# EEZ_tester_r1B3.net
KiCad netlist of a schematic drawn in EAGLE
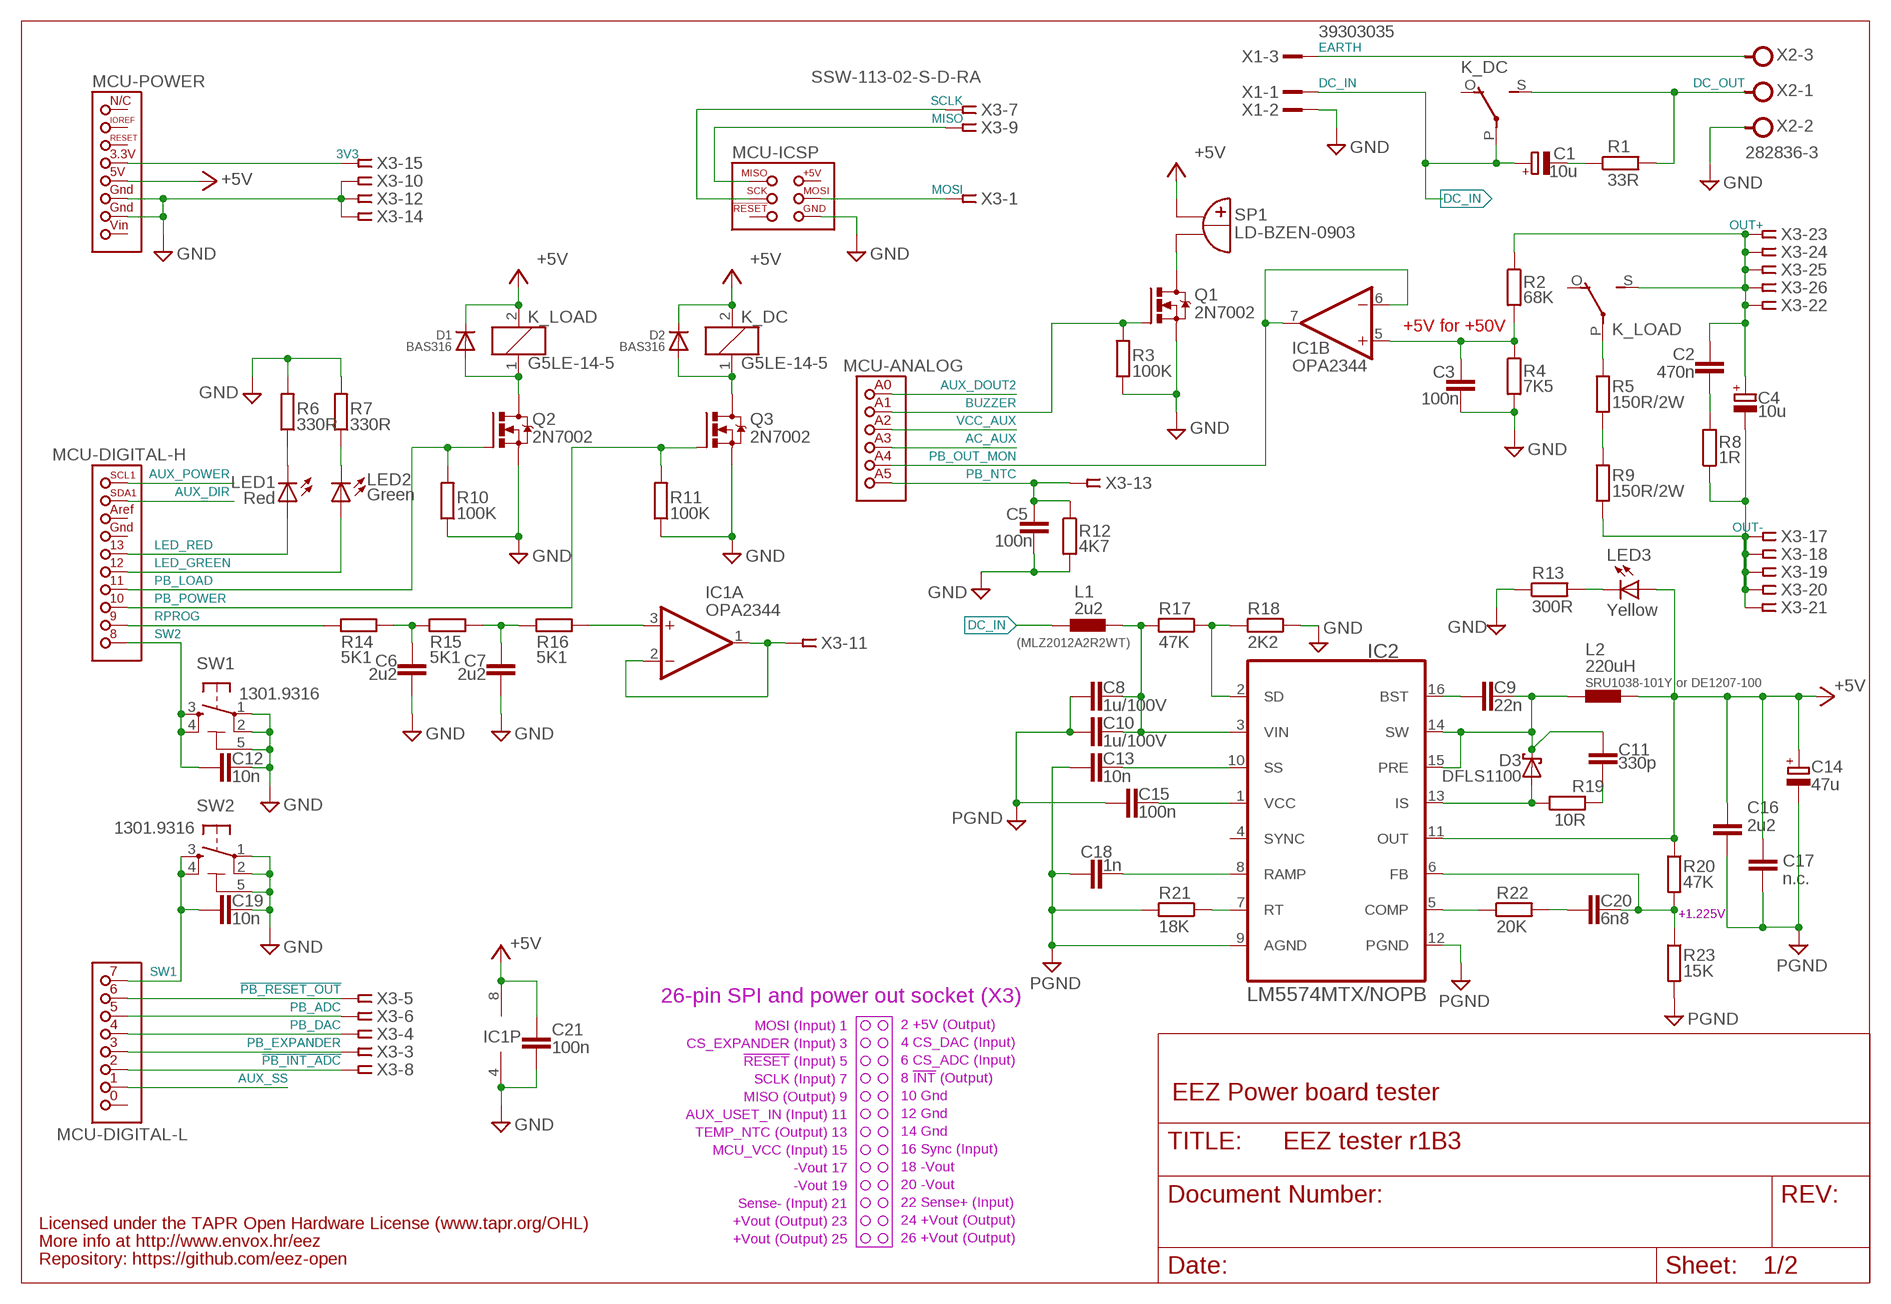
[diagram p0: schematic, sheet 1]
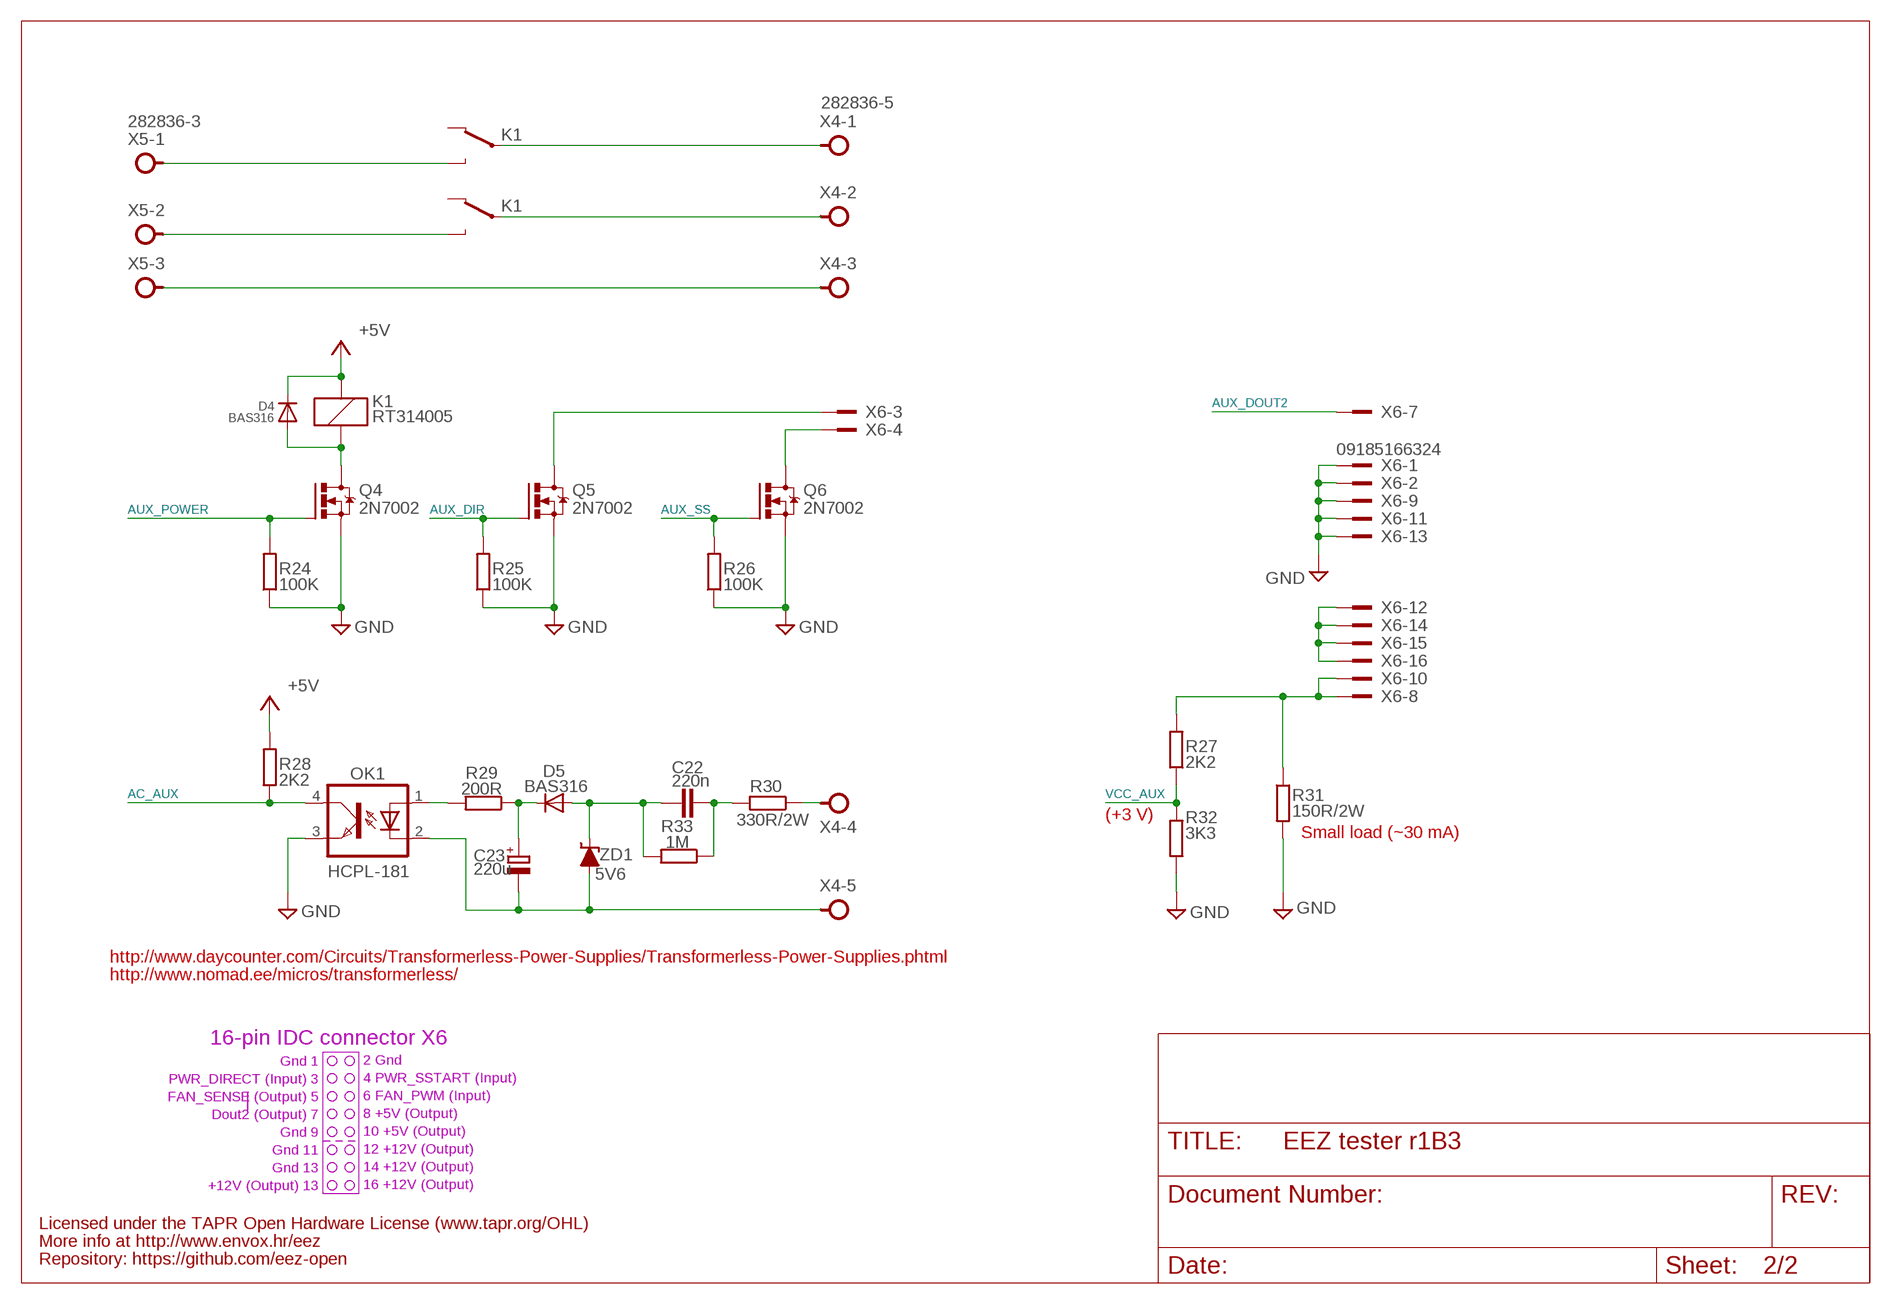
[diagram p1: schematic, sheet 2]

(export (version "E")
  (design (tool "Eeschema 10.0.6"))
  (components
    (comp (ref "C22")
      (value "220n")
      (footprint "eagle-import:C150-084X183")
      (libsource (lib "eagle-import") (part "C-EU150-084X183"))
    )
    (comp (ref "C23")
      (value "220u")
      (footprint "eagle-import:CAPAE660X610N")
      (libsource (lib "eagle-import") (part "ECAPPANASONIC_H"))
    )
    (comp (ref "D4")
      (value "BAS316")
      (footprint "eagle-import:SOD323-W")
      (libsource (lib "eagle-import") (part "DIODE-SOD323-W"))
    )
    (comp (ref "D5")
      (value "BAS316")
      (footprint "eagle-import:SOD323-W")
      (libsource (lib "eagle-import") (part "DIODE-SOD323-W"))
    )
    (comp (ref "K1")
      (value "RT314005")
      (footprint "eagle-import:RT-C_016A5_ROUND")
      (libsource (lib "eagle-import") (part "RELAY_RT314012-2"))
    )
    (comp (ref "OK1")
      (value "HCPL-181")
      (footprint "eagle-import:HCPL-181")
      (libsource (lib "eagle-import") (part "HCPL-181"))
    )
    (comp (ref "Q4")
      (value "2N7002")
      (footprint "eagle-import:SOT103P240X110-3N")
      (fields
        (field (name "MPN") "2N7002-7-F")
        (field (name "MPN_1") "2N7002-7-F")
        (field (name "OC_FARNELL") "1713823")
        (field (name "OC_NEWARK") "25R5679")
        (field (name "PACKAGE") "SOT-23-3")
        (field (name "SUPPLIER") "DIODES INC.")
      )
      (libsource (lib "eagle-import") (part "2N7002"))
    )
    (comp (ref "Q5")
      (value "2N7002")
      (footprint "eagle-import:SOT103P240X110-3N")
      (fields
        (field (name "MPN") "2N7002-7-F")
        (field (name "MPN_1") "2N7002-7-F")
        (field (name "OC_FARNELL") "1713823")
        (field (name "OC_NEWARK") "25R5679")
        (field (name "PACKAGE") "SOT-23-3")
        (field (name "SUPPLIER") "DIODES INC.")
      )
      (libsource (lib "eagle-import") (part "2N7002"))
    )
    (comp (ref "Q6")
      (value "2N7002")
      (footprint "eagle-import:SOT103P240X110-3N")
      (fields
        (field (name "MPN") "2N7002-7-F")
        (field (name "MPN_1") "2N7002-7-F")
        (field (name "OC_FARNELL") "1713823")
        (field (name "OC_NEWARK") "25R5679")
        (field (name "PACKAGE") "SOT-23-3")
        (field (name "SUPPLIER") "DIODES INC.")
      )
      (libsource (lib "eagle-import") (part "2N7002"))
    )
    (comp (ref "R24")
      (value "100K")
      (footprint "eagle-import:R0805")
      (libsource (lib "eagle-import") (part "R-EU_R0805"))
    )
    (comp (ref "R25")
      (value "100K")
      (footprint "eagle-import:R0805")
      (libsource (lib "eagle-import") (part "R-EU_R0805"))
    )
    (comp (ref "R26")
      (value "100K")
      (footprint "eagle-import:R0805")
      (libsource (lib "eagle-import") (part "R-EU_R0805"))
    )
    (comp (ref "R27")
      (value "2K2")
      (footprint "eagle-import:R0805")
      (libsource (lib "eagle-import") (part "R-EU_R0805"))
    )
    (comp (ref "R28")
      (value "2K2")
      (footprint "eagle-import:R0805")
      (libsource (lib "eagle-import") (part "R-EU_R0805"))
    )
    (comp (ref "R29")
      (value "200R")
      (footprint "eagle-import:R0805")
      (libsource (lib "eagle-import") (part "R-EU_R0805"))
    )
    (comp (ref "R30")
      (value "330R/2W")
      (footprint "eagle-import:R2512")
      (libsource (lib "eagle-import") (part "R-EU_R2512"))
    )
    (comp (ref "R31")
      (value "150R/2W")
      (footprint "eagle-import:R2512")
      (libsource (lib "eagle-import") (part "R-EU_R2512"))
    )
    (comp (ref "R32")
      (value "3K3")
      (footprint "eagle-import:R0805")
      (libsource (lib "eagle-import") (part "R-EU_R0805"))
    )
    (comp (ref "R33")
      (value "1M")
      (footprint "eagle-import:R0805")
      (libsource (lib "eagle-import") (part "R-EU_R0805"))
    )
    (comp (ref "X4")
      (value "282836-5")
      (footprint "eagle-import:TBLOCK5.0_5")
      (libsource (lib "eagle-import") (part "TBLOCK5.0_5A"))
    )
    (comp (ref "X5")
      (value "282836-3")
      (footprint "eagle-import:TBLOCK5.0_3")
      (libsource (lib "eagle-import") (part "TBLOCK5.0_3A"))
    )
    (comp (ref "X6")
      (value "09185166324")
      (footprint "eagle-import:IDC-16PIN")
      (libsource (lib "eagle-import") (part "IDC-16PIN"))
    )
    (comp (ref "ZD1")
      (value "5V6")
      (footprint "eagle-import:SOD323-W")
      (libsource (lib "eagle-import") (part "ZENER-DIODESOD323"))
    )
    (comp (ref "C1")
      (value "10u")
      (footprint "eagle-import:PANASONIC_C")
      (libsource (lib "eagle-import") (part "MyLib6_ECAPPANASONIC_C"))
    )
    (comp (ref "C2")
      (value "470n")
      (footprint "eagle-import:C0805")
      (libsource (lib "eagle-import") (part "C-EUC0805"))
    )
    (comp (ref "C3")
      (value "100n")
      (footprint "eagle-import:C0603")
      (libsource (lib "eagle-import") (part "C-EUC0603"))
    )
    (comp (ref "C4")
      (value "10u")
      (footprint "eagle-import:PANASONIC_C")
      (libsource (lib "eagle-import") (part "MyLib6_ECAPPANASONIC_C"))
    )
    (comp (ref "C5")
      (value "100n")
      (footprint "eagle-import:C0603")
      (libsource (lib "eagle-import") (part "C-EUC0603"))
    )
    (comp (ref "C6")
      (value "2u2")
      (footprint "eagle-import:C0805")
      (libsource (lib "eagle-import") (part "C-EUC0805"))
    )
    (comp (ref "C7")
      (value "2u2")
      (footprint "eagle-import:C0805")
      (libsource (lib "eagle-import") (part "C-EUC0805"))
    )
    (comp (ref "C8")
      (value "1u/100V")
      (footprint "eagle-import:C1206")
      (libsource (lib "eagle-import") (part "C-EUC1206"))
    )
    (comp (ref "C9")
      (value "22n")
      (footprint "eagle-import:C0805")
      (libsource (lib "eagle-import") (part "C-EUC0805"))
    )
    (comp (ref "C10")
      (value "1u/100V")
      (footprint "eagle-import:C1206")
      (libsource (lib "eagle-import") (part "C-EUC1206"))
    )
    (comp (ref "C11")
      (value "330p")
      (footprint "eagle-import:C0805")
      (libsource (lib "eagle-import") (part "C-EUC0805"))
    )
    (comp (ref "C12")
      (value "10n")
      (footprint "eagle-import:C0805")
      (libsource (lib "eagle-import") (part "C-EUC0805"))
    )
    (comp (ref "C13")
      (value "10n")
      (footprint "eagle-import:C0805")
      (libsource (lib "eagle-import") (part "C-EUC0805"))
    )
    (comp (ref "C14")
      (value "47u")
      (footprint "eagle-import:CAPAE660X610N")
      (libsource (lib "eagle-import") (part "ECAPPANASONIC_H"))
    )
    (comp (ref "C15")
      (value "100n")
      (footprint "eagle-import:C0603")
      (libsource (lib "eagle-import") (part "C-EUC0603"))
    )
    (comp (ref "C16")
      (value "2u2")
      (footprint "eagle-import:C0805")
      (libsource (lib "eagle-import") (part "C-EUC0805"))
    )
    (comp (ref "C17")
      (value "n.c.")
      (footprint "eagle-import:C0805")
      (libsource (lib "eagle-import") (part "C-EUC0805"))
    )
    (comp (ref "C18")
      (value "1n")
      (footprint "eagle-import:C0805")
      (libsource (lib "eagle-import") (part "C-EUC0805"))
    )
    (comp (ref "C19")
      (value "10n")
      (footprint "eagle-import:C0805")
      (libsource (lib "eagle-import") (part "C-EUC0805"))
    )
    (comp (ref "C20")
      (value "6n8")
      (footprint "eagle-import:C0805")
      (libsource (lib "eagle-import") (part "C-EUC0805"))
    )
    (comp (ref "C21")
      (value "100n")
      (footprint "eagle-import:C0603")
      (libsource (lib "eagle-import") (part "C-EUC0603"))
    )
    (comp (ref "D1")
      (value "BAS316")
      (footprint "eagle-import:SOD323-W")
      (libsource (lib "eagle-import") (part "DIODE-SOD323-W"))
    )
    (comp (ref "D2")
      (value "BAS316")
      (footprint "eagle-import:SOD323-W")
      (libsource (lib "eagle-import") (part "DIODE-SOD323-W"))
    )
    (comp (ref "D3")
      (value "DFLS1100")
      (footprint "eagle-import:SOD123")
      (libsource (lib "eagle-import") (part "SCHOTTKYSOD123"))
    )
    (comp (ref "IC1")
      (value "OPA2344")
      (footprint "eagle-import:SOIC127P600X173-8N")
      (libsource (lib "eagle-import") (part "TL072SOIC8"))
    )
    (comp (ref "IC2")
      (value "LM5574MTX/NOPB")
      (footprint "eagle-import:SOP65P640X110-16N")
      (fields (field (name "MPN") "LM5574MT"))
      (libsource (lib "eagle-import") (part "LM5574"))
    )
    (comp (ref "K_DC")
      (value "G5LE-14-5")
      (footprint "eagle-import:G5LE")
      (fields (field (name "OC_FARNELL") "unknown") (field (name "OC_NEWARK") "unknown"))
      (libsource (lib "eagle-import") (part "G5LE"))
    )
    (comp (ref "K_LOAD")
      (value "G5LE-14-5")
      (footprint "eagle-import:G5LE")
      (libsource (lib "eagle-import") (part "G5LE"))
    )
    (comp (ref "L1")
      (value "2u2")
      (footprint "eagle-import:0805")
      (libsource (lib "eagle-import") (part "L-EU0805"))
    )
    (comp (ref "L2")
      (value "220uH")
      (footprint "eagle-import:MSS1278")
      (libsource (lib "eagle-import") (part "COILCRAFT_MSS1278"))
    )
    (comp (ref "LED1")
      (value "Red")
      (footprint "eagle-import:LED3MM")
      (libsource (lib "eagle-import") (part "LED3MM"))
    )
    (comp (ref "LED2")
      (value "Green")
      (footprint "eagle-import:LED3MM")
      (libsource (lib "eagle-import") (part "LED3MM"))
    )
    (comp (ref "LED3")
      (value "Yellow")
      (footprint "eagle-import:LED3MM")
      (libsource (lib "eagle-import") (part "LED3MM"))
    )
    (comp (ref "MCU")
      (value "ARDUINO_LEONARDO")
      (footprint "eagle-import:ARDUINO_LEONARDO")
      (libsource (lib "eagle-import") (part "ARDUINO_LEONARDO"))
    )
    (comp (ref "Q1")
      (value "2N7002")
      (footprint "eagle-import:SOT103P240X110-3N")
      (fields (field (name "MPN") "2N7002-7-F"))
      (libsource (lib "eagle-import") (part "2N7002"))
    )
    (comp (ref "Q2")
      (value "2N7002")
      (footprint "eagle-import:SOT103P240X110-3N")
      (fields
        (field (name "MPN") "2N7002-7-F")
        (field (name "MPN_1") "2N7002-7-F")
        (field (name "OC_FARNELL") "1713823")
        (field (name "OC_NEWARK") "25R5679")
        (field (name "PACKAGE") "SOT-23-3")
        (field (name "SUPPLIER") "DIODES INC.")
      )
      (libsource (lib "eagle-import") (part "2N7002"))
    )
    (comp (ref "Q3")
      (value "2N7002")
      (footprint "eagle-import:SOT103P240X110-3N")
      (fields
        (field (name "MPN") "2N7002-7-F")
        (field (name "MPN_1") "2N7002-7-F")
        (field (name "OC_FARNELL") "1713823")
        (field (name "OC_NEWARK") "25R5679")
        (field (name "PACKAGE") "SOT-23-3")
        (field (name "SUPPLIER") "DIODES INC.")
      )
      (libsource (lib "eagle-import") (part "2N7002"))
    )
    (comp (ref "R1")
      (value "33R")
      (footprint "eagle-import:R0805")
      (libsource (lib "eagle-import") (part "R-EU_R0805"))
    )
    (comp (ref "R2")
      (value "68K")
      (footprint "eagle-import:R0805")
      (libsource (lib "eagle-import") (part "R-EU_R0805"))
    )
    (comp (ref "R3")
      (value "100K")
      (footprint "eagle-import:R0805")
      (libsource (lib "eagle-import") (part "R-EU_R0805"))
    )
    (comp (ref "R4")
      (value "7K5")
      (footprint "eagle-import:R0805")
      (libsource (lib "eagle-import") (part "R-EU_R0805"))
    )
    (comp (ref "R5")
      (value "150R/2W")
      (footprint "eagle-import:0617_22")
      (libsource (lib "eagle-import") (part "R-EU_0617/22"))
    )
    (comp (ref "R6")
      (value "330R")
      (footprint "eagle-import:R0805")
      (libsource (lib "eagle-import") (part "R-EU_R0805"))
    )
    (comp (ref "R7")
      (value "330R")
      (footprint "eagle-import:R0805")
      (libsource (lib "eagle-import") (part "R-EU_R0805"))
    )
    (comp (ref "R8")
      (value "1R")
      (footprint "eagle-import:R0805")
      (libsource (lib "eagle-import") (part "R-EU_R0805"))
    )
    (comp (ref "R9")
      (value "150R/2W")
      (footprint "eagle-import:0617_22")
      (libsource (lib "eagle-import") (part "R-EU_0617/22"))
    )
    (comp (ref "R10")
      (value "100K")
      (footprint "eagle-import:R0805")
      (libsource (lib "eagle-import") (part "R-EU_R0805"))
    )
    (comp (ref "R11")
      (value "100K")
      (footprint "eagle-import:R0805")
      (libsource (lib "eagle-import") (part "R-EU_R0805"))
    )
    (comp (ref "R12")
      (value "4K7")
      (footprint "eagle-import:R0805")
      (libsource (lib "eagle-import") (part "R-EU_R0805"))
    )
    (comp (ref "R13")
      (value "300R")
      (footprint "eagle-import:R0805")
      (libsource (lib "eagle-import") (part "R-EU_R0805"))
    )
    (comp (ref "R14")
      (value "5K1")
      (footprint "eagle-import:R0805")
      (libsource (lib "eagle-import") (part "R-EU_R0805"))
    )
    (comp (ref "R15")
      (value "5K1")
      (footprint "eagle-import:R0805")
      (libsource (lib "eagle-import") (part "R-EU_R0805"))
    )
    (comp (ref "R16")
      (value "5K1")
      (footprint "eagle-import:R0805")
      (libsource (lib "eagle-import") (part "R-EU_R0805"))
    )
    (comp (ref "R17")
      (value "47K")
      (footprint "eagle-import:R0805")
      (libsource (lib "eagle-import") (part "R-EU_R0805"))
    )
    (comp (ref "R18")
      (value "2K2")
      (footprint "eagle-import:R0805")
      (libsource (lib "eagle-import") (part "R-EU_R0805"))
    )
    (comp (ref "R19")
      (value "10R")
      (footprint "eagle-import:R1206")
      (libsource (lib "eagle-import") (part "R-EU_R1206"))
    )
    (comp (ref "R20")
      (value "47K")
      (footprint "eagle-import:R0805")
      (libsource (lib "eagle-import") (part "R-EU_R0805"))
    )
    (comp (ref "R21")
      (value "18K")
      (footprint "eagle-import:R0805")
      (libsource (lib "eagle-import") (part "R-EU_R0805"))
    )
    (comp (ref "R22")
      (value "20K")
      (footprint "eagle-import:R0805")
      (libsource (lib "eagle-import") (part "R-EU_R0805"))
    )
    (comp (ref "R23")
      (value "15K")
      (footprint "eagle-import:R0805")
      (libsource (lib "eagle-import") (part "R-EU_R0805"))
    )
    (comp (ref "SP1")
      (value "LD-BZEN-0903")
      (footprint "eagle-import:LD-BZEN-0903")
      (libsource (lib "eagle-import") (part "BUZZER-2"))
    )
    (comp (ref "SW1")
      (value "1301.9316")
      (footprint "eagle-import:TACTM-6XN")
      (libsource (lib "eagle-import") (part "TACT_SW"))
    )
    (comp (ref "SW2")
      (value "1301.9316")
      (footprint "eagle-import:TACTM-6XN")
      (libsource (lib "eagle-import") (part "TACT_SW"))
    )
    (comp (ref "X1")
      (value "39303035")
      (footprint "eagle-import:MINIFIT_6659-3")
      (libsource (lib "eagle-import") (part "MINIFIT-3PIN"))
    )
    (comp (ref "X2")
      (value "282836-3")
      (footprint "eagle-import:TBLOCK5.0_3")
      (libsource (lib "eagle-import") (part "TBLOCK5.0_3A"))
    )
    (comp (ref "X3")
      (value "SSW-113-02-S-D-RA")
      (footprint "eagle-import:TSW-113-02-S-D-RA")
      (libsource (lib "eagle-import") (part "SSW-113-02-S-D-RA"))
    )
  )
  (nets
    (net (code "1") (name "+5V") (class "Default")
      (node (ref "C14") (pin "1") (pinfunction "+_1") (pintype "passive"))
      (node (ref "C16") (pin "1") (pinfunction "1_1") (pintype "passive"))
      (node (ref "C17") (pin "1") (pinfunction "1_1") (pintype "passive"))
      (node (ref "C21") (pin "1") (pinfunction "1_1") (pintype "passive"))
      (node (ref "D1") (pin "C") (pinfunction "C_C") (pintype "passive"))
      (node (ref "D2") (pin "C") (pinfunction "C_C") (pintype "passive"))
      (node (ref "D4") (pin "C") (pinfunction "C_C") (pintype "passive"))
      (node (ref "IC1") (pin "8") (pinfunction "V+_8") (pintype "power_in"))
      (node (ref "IC2") (pin "11") (pinfunction "OUT_11") (pintype "output"))
      (node (ref "K1") (pin "A2") (pinfunction "C1_A2") (pintype "passive"))
      (node (ref "K_DC") (pin "2") (pinfunction "2_2") (pintype "passive"))
      (node (ref "K_LOAD") (pin "2") (pinfunction "2_2") (pintype "passive"))
      (node (ref "L2") (pin "2") (pinfunction "2_2") (pintype "passive"))
      (node (ref "LED3") (pin "A") (pinfunction "A_A") (pintype "passive"))
      (node (ref "MCU") (pin "5V") (pinfunction "5V_5V") (pintype "bidirectional"))
      (node (ref "R20") (pin "1") (pinfunction "1_1") (pintype "passive"))
      (node (ref "R28") (pin "2") (pinfunction "2_2") (pintype "passive"))
      (node (ref "SP1") (pin "+B") (pinfunction "+_+B") (pintype "passive"))
    )
    (net (code "2") (name "3V3") (class "Default")
      (node (ref "MCU") (pin "3.3V") (pinfunction "3V3_3.3V") (pintype "bidirectional"))
      (node (ref "X3") (pin "15") (pinfunction "1_15") (pintype "passive"))
    )
    (net (code "3") (name "AC_AUX") (class "Default")
      (node (ref "MCU") (pin "A3") (pinfunction "ADC3_A3") (pintype "bidirectional"))
      (node (ref "OK1") (pin "4") (pinfunction "COL_4") (pintype "passive"))
      (node (ref "R28") (pin "1") (pinfunction "1_1") (pintype "passive"))
    )
    (net (code "4") (name "AUX_DIR") (class "Default")
      (node (ref "MCU") (pin "SDA1") (pinfunction "SDA1_SDA1") (pintype "bidirectional"))
      (node (ref "Q5") (pin "1") (pinfunction "G_1") (pintype "passive"))
      (node (ref "R25") (pin "2") (pinfunction "2_2") (pintype "passive"))
    )
    (net (code "5") (name "AUX_DOUT2") (class "Default")
      (node (ref "MCU") (pin "A0") (pinfunction "ADC0_A0") (pintype "bidirectional"))
      (node (ref "X6") (pin "7") (pinfunction "1_7") (pintype "passive"))
    )
    (net (code "6") (name "AUX_POWER") (class "Default")
      (node (ref "MCU") (pin "SCL1") (pinfunction "SCL1_SCL1") (pintype "bidirectional"))
      (node (ref "Q4") (pin "1") (pinfunction "G_1") (pintype "passive"))
      (node (ref "R24") (pin "2") (pinfunction "2_2") (pintype "passive"))
    )
    (net (code "7") (name "AUX_SS") (class "Default")
      (node (ref "MCU") (pin "1") (pinfunction "1(PE1)_1") (pintype "bidirectional"))
      (node (ref "Q6") (pin "1") (pinfunction "G_1") (pintype "passive"))
      (node (ref "R26") (pin "2") (pinfunction "2_2") (pintype "passive"))
    )
    (net (code "8") (name "BUZZER") (class "Default")
      (node (ref "MCU") (pin "A1") (pinfunction "ADC1_A1") (pintype "bidirectional"))
      (node (ref "Q1") (pin "1") (pinfunction "G_1") (pintype "passive"))
      (node (ref "R3") (pin "2") (pinfunction "2_2") (pintype "passive"))
    )
    (net (code "9") (name "DC_IN") (class "Default")
      (node (ref "C1") (pin "1") (pinfunction "+_1") (pintype "passive"))
      (node (ref "K_DC") (pin "P") (pinfunction "P_P") (pintype "passive"))
      (node (ref "L1") (pin "1") (pinfunction "1_1") (pintype "passive"))
      (node (ref "X1") (pin "1") (pinfunction "1_1") (pintype "passive"))
    )
    (net (code "10") (name "DC_OUT") (class "Default")
      (node (ref "K_DC") (pin "S") (pinfunction "S_S") (pintype "passive"))
      (node (ref "R1") (pin "2") (pinfunction "2_2") (pintype "passive"))
      (node (ref "X2") (pin "1") (pinfunction "1_1") (pintype "bidirectional"))
    )
    (net (code "11") (name "EARTH") (class "Default")
      (node (ref "X1") (pin "3") (pinfunction "1_3") (pintype "passive"))
      (node (ref "X2") (pin "3") (pinfunction "1_3") (pintype "bidirectional"))
    )
    (net (code "12") (name "GND") (class "Default")
      (node (ref "C10") (pin "2") (pinfunction "2_2") (pintype "passive"))
      (node (ref "C12") (pin "2") (pinfunction "2_2") (pintype "passive"))
      (node (ref "C13") (pin "2") (pinfunction "2_2") (pintype "passive"))
      (node (ref "C14") (pin "2") (pinfunction "-_2") (pintype "passive"))
      (node (ref "C15") (pin "1") (pinfunction "1_1") (pintype "passive"))
      (node (ref "C16") (pin "2") (pinfunction "2_2") (pintype "passive"))
      (node (ref "C17") (pin "2") (pinfunction "2_2") (pintype "passive"))
      (node (ref "C18") (pin "1") (pinfunction "1_1") (pintype "passive"))
      (node (ref "C19") (pin "2") (pinfunction "2_2") (pintype "passive"))
      (node (ref "C21") (pin "2") (pinfunction "2_2") (pintype "passive"))
      (node (ref "C3") (pin "1") (pinfunction "1_1") (pintype "passive"))
      (node (ref "C5") (pin "1") (pinfunction "1_1") (pintype "passive"))
      (node (ref "C6") (pin "2") (pinfunction "2_2") (pintype "passive"))
      (node (ref "C7") (pin "2") (pinfunction "2_2") (pintype "passive"))
      (node (ref "C8") (pin "2") (pinfunction "2_2") (pintype "passive"))
      (node (ref "IC1") (pin "4") (pinfunction "V-_4") (pintype "power_in"))
      (node (ref "IC2") (pin "12") (pinfunction "PGND_12") (pintype "passive"))
      (node (ref "IC2") (pin "9") (pinfunction "AGND_9") (pintype "passive"))
      (node (ref "MCU") (pin "GND1") (pinfunction "GND1_GND1") (pintype "bidirectional"))
      (node (ref "MCU") (pin "GND2") (pinfunction "GND2_GND2") (pintype "bidirectional"))
      (node (ref "MCU") (pin "ICSP_GND") (pinfunction "GND_ICSP_GND") (pintype "bidirectional"))
      (node (ref "OK1") (pin "3") (pinfunction "EMIT_3") (pintype "passive"))
      (node (ref "Q1") (pin "2") (pinfunction "S_2") (pintype "passive"))
      (node (ref "Q2") (pin "2") (pinfunction "S_2") (pintype "passive"))
      (node (ref "Q3") (pin "2") (pinfunction "S_2") (pintype "passive"))
      (node (ref "Q4") (pin "2") (pinfunction "S_2") (pintype "passive"))
      (node (ref "Q5") (pin "2") (pinfunction "S_2") (pintype "passive"))
      (node (ref "Q6") (pin "2") (pinfunction "S_2") (pintype "passive"))
      (node (ref "R10") (pin "1") (pinfunction "1_1") (pintype "passive"))
      (node (ref "R11") (pin "1") (pinfunction "1_1") (pintype "passive"))
      (node (ref "R12") (pin "2") (pinfunction "2_2") (pintype "passive"))
      (node (ref "R13") (pin "1") (pinfunction "1_1") (pintype "passive"))
      (node (ref "R18") (pin "1") (pinfunction "1_1") (pintype "passive"))
      (node (ref "R21") (pin "2") (pinfunction "2_2") (pintype "passive"))
      (node (ref "R23") (pin "2") (pinfunction "2_2") (pintype "passive"))
      (node (ref "R24") (pin "1") (pinfunction "1_1") (pintype "passive"))
      (node (ref "R25") (pin "1") (pinfunction "1_1") (pintype "passive"))
      (node (ref "R26") (pin "1") (pinfunction "1_1") (pintype "passive"))
      (node (ref "R3") (pin "1") (pinfunction "1_1") (pintype "passive"))
      (node (ref "R31") (pin "2") (pinfunction "2_2") (pintype "passive"))
      (node (ref "R32") (pin "1") (pinfunction "1_1") (pintype "passive"))
      (node (ref "R4") (pin "2") (pinfunction "2_2") (pintype "passive"))
      (node (ref "R6") (pin "2") (pinfunction "2_2") (pintype "passive"))
      (node (ref "R7") (pin "2") (pinfunction "2_2") (pintype "passive"))
      (node (ref "SW1") (pin "1") (pinfunction "1_1") (pintype "passive"))
      (node (ref "SW1") (pin "2") (pinfunction "2_2") (pintype "passive"))
      (node (ref "SW1") (pin "5") (pinfunction "5-GND_5") (pintype "passive"))
      (node (ref "SW2") (pin "1") (pinfunction "1_1") (pintype "passive"))
      (node (ref "SW2") (pin "2") (pinfunction "2_2") (pintype "passive"))
      (node (ref "SW2") (pin "5") (pinfunction "5-GND_5") (pintype "passive"))
      (node (ref "X1") (pin "2") (pinfunction "1_2") (pintype "passive"))
      (node (ref "X2") (pin "2") (pinfunction "1_2") (pintype "bidirectional"))
      (node (ref "X3") (pin "10") (pinfunction "1_10") (pintype "passive"))
      (node (ref "X3") (pin "12") (pinfunction "1_12") (pintype "passive"))
      (node (ref "X3") (pin "14") (pinfunction "1_14") (pintype "passive"))
      (node (ref "X6") (pin "1") (pinfunction "1_1") (pintype "passive"))
      (node (ref "X6") (pin "11") (pinfunction "1_11") (pintype "passive"))
      (node (ref "X6") (pin "13") (pinfunction "1_13") (pintype "passive"))
      (node (ref "X6") (pin "2") (pinfunction "1_2") (pintype "passive"))
      (node (ref "X6") (pin "9") (pinfunction "1_9") (pintype "passive"))
    )
    (net (code "13") (name "LED_GREEN") (class "Default")
      (node (ref "LED2") (pin "A") (pinfunction "A_A") (pintype "passive"))
      (node (ref "MCU") (pin "12") (pinfunction "12_12") (pintype "bidirectional"))
    )
    (net (code "14") (name "LED_RED") (class "Default")
      (node (ref "LED1") (pin "A") (pinfunction "A_A") (pintype "passive"))
      (node (ref "MCU") (pin "13") (pinfunction "13_13") (pintype "bidirectional"))
    )
    (net (code "15") (name "MISO") (class "Default")
      (node (ref "MCU") (pin "ICSP_MISO") (pinfunction "MISO_ICSP_MISO") (pintype "bidirectional"))
      (node (ref "X3") (pin "9") (pinfunction "1_9") (pintype "passive"))
    )
    (net (code "16") (name "MOSI") (class "Default")
      (node (ref "MCU") (pin "ICSP_MOSI") (pinfunction "MOSI_ICSP_MOSI") (pintype "bidirectional"))
      (node (ref "X3") (pin "1") (pinfunction "1_1") (pintype "passive"))
    )
    (net (code "17") (name "Net-(C1--)") (class "Default")
      (node (ref "C1") (pin "2") (pinfunction "-_2") (pintype "passive"))
      (node (ref "R1") (pin "1") (pinfunction "1_1") (pintype "passive"))
    )
    (net (code "18") (name "Net-(C2-Pad2)") (class "Default")
      (node (ref "C2") (pin "2") (pinfunction "2_2") (pintype "passive"))
      (node (ref "R8") (pin "2") (pinfunction "2_2") (pintype "passive"))
    )
    (net (code "19") (name "Net-(C6-Pad1)") (class "Default")
      (node (ref "C6") (pin "1") (pinfunction "1_1") (pintype "passive"))
      (node (ref "R14") (pin "1") (pinfunction "1_1") (pintype "passive"))
      (node (ref "R15") (pin "2") (pinfunction "2_2") (pintype "passive"))
    )
    (net (code "20") (name "Net-(C7-Pad1)") (class "Default")
      (node (ref "C7") (pin "1") (pinfunction "1_1") (pintype "passive"))
      (node (ref "R15") (pin "1") (pinfunction "1_1") (pintype "passive"))
      (node (ref "R16") (pin "2") (pinfunction "2_2") (pintype "passive"))
    )
    (net (code "21") (name "Net-(C11-Pad2)") (class "Default")
      (node (ref "C11") (pin "2") (pinfunction "2_2") (pintype "passive"))
      (node (ref "R19") (pin "2") (pinfunction "2_2") (pintype "passive"))
    )
    (net (code "22") (name "Net-(C20-Pad2)") (class "Default")
      (node (ref "C20") (pin "2") (pinfunction "2_2") (pintype "passive"))
      (node (ref "R22") (pin "2") (pinfunction "2_2") (pintype "passive"))
    )
    (net (code "23") (name "Net-(C22-Pad1)") (class "Default")
      (node (ref "C22") (pin "1") (pinfunction "1_1") (pintype "passive"))
      (node (ref "D5") (pin "A") (pinfunction "A_A") (pintype "passive"))
      (node (ref "R33") (pin "2") (pinfunction "2_2") (pintype "passive"))
      (node (ref "ZD1") (pin "C") (pinfunction "C_C") (pintype "passive"))
    )
    (net (code "24") (name "Net-(C22-Pad2)") (class "Default")
      (node (ref "C22") (pin "2") (pinfunction "2_2") (pintype "passive"))
      (node (ref "R30") (pin "2") (pinfunction "2_2") (pintype "passive"))
      (node (ref "R33") (pin "1") (pinfunction "1_1") (pintype "passive"))
    )
    (net (code "25") (name "Net-(C23-+)") (class "Default")
      (node (ref "C23") (pin "1") (pinfunction "+_1") (pintype "passive"))
      (node (ref "D5") (pin "C") (pinfunction "C_C") (pintype "passive"))
      (node (ref "R29") (pin "1") (pinfunction "1_1") (pintype "passive"))
    )
    (net (code "26") (name "Net-(C23--)") (class "Default")
      (node (ref "C23") (pin "2") (pinfunction "-_2") (pintype "passive"))
      (node (ref "OK1") (pin "2") (pinfunction "C_2") (pintype "passive"))
      (node (ref "X4") (pin "5") (pinfunction "1_5") (pintype "bidirectional"))
      (node (ref "ZD1") (pin "A") (pinfunction "A_A") (pintype "passive"))
    )
    (net (code "27") (name "Net-(IC1A-+IN)") (class "Default")
      (node (ref "IC1") (pin "3") (pinfunction "+IN_3") (pintype "input"))
      (node (ref "R16") (pin "1") (pinfunction "1_1") (pintype "passive"))
    )
    (net (code "28") (name "Net-(IC1A--IN)") (class "Default")
      (node (ref "IC1") (pin "1") (pinfunction "OUT_1") (pintype "output"))
      (node (ref "IC1") (pin "2") (pinfunction "-IN_2") (pintype "input"))
      (node (ref "X3") (pin "11") (pinfunction "1_11") (pintype "passive"))
    )
    (net (code "29") (name "Net-(IC1B-+IN)") (class "Default")
      (node (ref "C3") (pin "2") (pinfunction "2_2") (pintype "passive"))
      (node (ref "IC1") (pin "5") (pinfunction "+IN_5") (pintype "input"))
      (node (ref "R2") (pin "2") (pinfunction "2_2") (pintype "passive"))
      (node (ref "R4") (pin "1") (pinfunction "1_1") (pintype "passive"))
    )
    (net (code "30") (name "Net-(IC2-BST)") (class "Default")
      (node (ref "C9") (pin "2") (pinfunction "2_2") (pintype "passive"))
      (node (ref "IC2") (pin "16") (pinfunction "BST_16") (pintype "input"))
    )
    (net (code "31") (name "Net-(IC2-COMP)") (class "Default")
      (node (ref "IC2") (pin "5") (pinfunction "COMP_5") (pintype "input"))
      (node (ref "R22") (pin "1") (pinfunction "1_1") (pintype "passive"))
    )
    (net (code "32") (name "Net-(IC2-FB)") (class "Default")
      (node (ref "C20") (pin "1") (pinfunction "1_1") (pintype "passive"))
      (node (ref "IC2") (pin "6") (pinfunction "FB_6") (pintype "input"))
      (node (ref "R20") (pin "2") (pinfunction "2_2") (pintype "passive"))
      (node (ref "R23") (pin "1") (pinfunction "1_1") (pintype "passive"))
    )
    (net (code "33") (name "Net-(IC2-IS)") (class "Default")
      (node (ref "D3") (pin "A") (pinfunction "A_A") (pintype "passive"))
      (node (ref "IC2") (pin "13") (pinfunction "IS_13") (pintype "input"))
      (node (ref "R19") (pin "1") (pinfunction "1_1") (pintype "passive"))
    )
    (net (code "34") (name "Net-(IC2-PRE)") (class "Default")
      (node (ref "C11") (pin "1") (pinfunction "1_1") (pintype "passive"))
      (node (ref "C9") (pin "1") (pinfunction "1_1") (pintype "passive"))
      (node (ref "D3") (pin "C") (pinfunction "C_C") (pintype "passive"))
      (node (ref "IC2") (pin "14") (pinfunction "SW_14") (pintype "output"))
      (node (ref "IC2") (pin "15") (pinfunction "PRE_15") (pintype "input"))
      (node (ref "L2") (pin "1") (pinfunction "1_1") (pintype "passive"))
    )
    (net (code "35") (name "Net-(IC2-RAMP)") (class "Default")
      (node (ref "C18") (pin "2") (pinfunction "2_2") (pintype "passive"))
      (node (ref "IC2") (pin "8") (pinfunction "RAMP_8") (pintype "input"))
    )
    (net (code "36") (name "Net-(IC2-RT)") (class "Default")
      (node (ref "IC2") (pin "7") (pinfunction "RT_7") (pintype "input"))
      (node (ref "R21") (pin "1") (pinfunction "1_1") (pintype "passive"))
    )
    (net (code "37") (name "Net-(IC2-SD)") (class "Default")
      (node (ref "IC2") (pin "2") (pinfunction "SD_2") (pintype "input"))
      (node (ref "R17") (pin "1") (pinfunction "1_1") (pintype "passive"))
      (node (ref "R18") (pin "2") (pinfunction "2_2") (pintype "passive"))
    )
    (net (code "38") (name "Net-(IC2-SS)") (class "Default")
      (node (ref "C13") (pin "1") (pinfunction "1_1") (pintype "passive"))
      (node (ref "IC2") (pin "10") (pinfunction "SS_10") (pintype "input"))
    )
    (net (code "39") (name "Net-(IC2-VCC)") (class "Default")
      (node (ref "C15") (pin "2") (pinfunction "2_2") (pintype "passive"))
      (node (ref "IC2") (pin "1") (pinfunction "VCC_1") (pintype "power_in"))
    )
    (net (code "40") (name "Net-(IC2-VIN)") (class "Default")
      (node (ref "C10") (pin "1") (pinfunction "1_1") (pintype "passive"))
      (node (ref "C8") (pin "1") (pinfunction "1_1") (pintype "passive"))
      (node (ref "IC2") (pin "3") (pinfunction "VIN_3") (pintype "input"))
      (node (ref "L1") (pin "2") (pinfunction "2_2") (pintype "passive"))
      (node (ref "R17") (pin "2") (pinfunction "2_2") (pintype "passive"))
    )
    (net (code "41") (name "Net-(K1A-O)") (class "Default")
      (node (ref "K1") (pin "14A") (pinfunction "O_14A") (pintype "passive"))
      (node (ref "X5") (pin "2") (pinfunction "1_2") (pintype "bidirectional"))
    )
    (net (code "42") (name "Net-(K1A-P)") (class "Default")
      (node (ref "K1") (pin "11A") (pinfunction "P_11A") (pintype "passive"))
      (node (ref "X4") (pin "2") (pinfunction "1_2") (pintype "bidirectional"))
    )
    (net (code "43") (name "Net-(K1B-O)") (class "Default")
      (node (ref "K1") (pin "14B") (pinfunction "O_14B") (pintype "passive"))
      (node (ref "X5") (pin "1") (pinfunction "1_1") (pintype "bidirectional"))
    )
    (net (code "44") (name "Net-(K1B-P)") (class "Default")
      (node (ref "K1") (pin "11B") (pinfunction "P_11B") (pintype "passive"))
      (node (ref "X4") (pin "1") (pinfunction "1_1") (pintype "bidirectional"))
    )
    (net (code "45") (name "Net-(K1C-C2)") (class "Default")
      (node (ref "D4") (pin "A") (pinfunction "A_A") (pintype "passive"))
      (node (ref "K1") (pin "A1") (pinfunction "C2_A1") (pintype "passive"))
      (node (ref "Q4") (pin "3") (pinfunction "D_3") (pintype "passive"))
    )
    (net (code "46") (name "Net-(K_LOAD-PadP)") (class "Default")
      (node (ref "K_LOAD") (pin "P") (pinfunction "P_P") (pintype "passive"))
      (node (ref "R5") (pin "2") (pinfunction "2_2") (pintype "passive"))
    )
    (net (code "47") (name "Net-(LED1-C)") (class "Default")
      (node (ref "LED1") (pin "K") (pinfunction "C_K") (pintype "passive"))
      (node (ref "R6") (pin "1") (pinfunction "1_1") (pintype "passive"))
    )
    (net (code "48") (name "Net-(LED2-C)") (class "Default")
      (node (ref "LED2") (pin "K") (pinfunction "C_K") (pintype "passive"))
      (node (ref "R7") (pin "1") (pinfunction "1_1") (pintype "passive"))
    )
    (net (code "49") (name "Net-(LED3-C)") (class "Default")
      (node (ref "LED3") (pin "K") (pinfunction "C_K") (pintype "passive"))
      (node (ref "R13") (pin "2") (pinfunction "2_2") (pintype "passive"))
    )
    (net (code "50") (name "Net-(OK1-A)") (class "Default")
      (node (ref "OK1") (pin "1") (pinfunction "A_1") (pintype "passive"))
      (node (ref "R29") (pin "2") (pinfunction "2_2") (pintype "passive"))
    )
    (net (code "51") (name "Net-(Q1-D)") (class "Default")
      (node (ref "Q1") (pin "3") (pinfunction "D_3") (pintype "passive"))
      (node (ref "SP1") (pin "-B") (pinfunction "-_-B") (pintype "passive"))
    )
    (net (code "52") (name "Net-(Q2-D)") (class "Default")
      (node (ref "D1") (pin "A") (pinfunction "A_A") (pintype "passive"))
      (node (ref "K_LOAD") (pin "1") (pinfunction "1_1") (pintype "passive"))
      (node (ref "Q2") (pin "3") (pinfunction "D_3") (pintype "passive"))
    )
    (net (code "53") (name "Net-(Q3-D)") (class "Default")
      (node (ref "D2") (pin "A") (pinfunction "A_A") (pintype "passive"))
      (node (ref "K_DC") (pin "1") (pinfunction "1_1") (pintype "passive"))
      (node (ref "Q3") (pin "3") (pinfunction "D_3") (pintype "passive"))
    )
    (net (code "54") (name "Net-(Q5-D)") (class "Default")
      (node (ref "Q5") (pin "3") (pinfunction "D_3") (pintype "passive"))
      (node (ref "X6") (pin "3") (pinfunction "1_3") (pintype "passive"))
    )
    (net (code "55") (name "Net-(Q6-D)") (class "Default")
      (node (ref "Q6") (pin "3") (pinfunction "D_3") (pintype "passive"))
      (node (ref "X6") (pin "4") (pinfunction "1_4") (pintype "passive"))
    )
    (net (code "56") (name "Net-(R5-Pad1)") (class "Default")
      (node (ref "R5") (pin "1") (pinfunction "1_1") (pintype "passive"))
      (node (ref "R9") (pin "2") (pinfunction "2_2") (pintype "passive"))
    )
    (net (code "57") (name "Net-(X4C-1)") (class "Default")
      (node (ref "X4") (pin "3") (pinfunction "1_3") (pintype "bidirectional"))
      (node (ref "X5") (pin "3") (pinfunction "1_3") (pintype "bidirectional"))
    )
    (net (code "58") (name "Net-(X4D-1)") (class "Default")
      (node (ref "R30") (pin "1") (pinfunction "1_1") (pintype "passive"))
      (node (ref "X4") (pin "4") (pinfunction "1_4") (pintype "bidirectional"))
    )
    (net (code "59") (name "Net-(X6B-1)") (class "Default")
      (node (ref "R27") (pin "2") (pinfunction "2_2") (pintype "passive"))
      (node (ref "R31") (pin "1") (pinfunction "1_1") (pintype "passive"))
      (node (ref "X6") (pin "10") (pinfunction "1_10") (pintype "passive"))
      (node (ref "X6") (pin "8") (pinfunction "1_8") (pintype "passive"))
    )
    (net (code "60") (name "Net-(X6D-1)") (class "Default")
      (node (ref "X6") (pin "12") (pinfunction "1_12") (pintype "passive"))
      (node (ref "X6") (pin "14") (pinfunction "1_14") (pintype "passive"))
      (node (ref "X6") (pin "15") (pinfunction "1_15") (pintype "passive"))
      (node (ref "X6") (pin "16") (pinfunction "1_16") (pintype "passive"))
    )
    (net (code "61") (name "OUT+") (class "Default")
      (node (ref "C2") (pin "1") (pinfunction "1_1") (pintype "passive"))
      (node (ref "C4") (pin "1") (pinfunction "+_1") (pintype "passive"))
      (node (ref "K_LOAD") (pin "S") (pinfunction "S_S") (pintype "passive"))
      (node (ref "R2") (pin "1") (pinfunction "1_1") (pintype "passive"))
      (node (ref "X3") (pin "22") (pinfunction "1_22") (pintype "passive"))
      (node (ref "X3") (pin "23") (pinfunction "1_23") (pintype "passive"))
      (node (ref "X3") (pin "24") (pinfunction "1_24") (pintype "passive"))
      (node (ref "X3") (pin "25") (pinfunction "1_25") (pintype "passive"))
      (node (ref "X3") (pin "26") (pinfunction "1_26") (pintype "passive"))
    )
    (net (code "62") (name "OUT-") (class "Default")
      (node (ref "C4") (pin "2") (pinfunction "-_2") (pintype "passive"))
      (node (ref "R8") (pin "1") (pinfunction "1_1") (pintype "passive"))
      (node (ref "R9") (pin "1") (pinfunction "1_1") (pintype "passive"))
      (node (ref "X3") (pin "17") (pinfunction "1_17") (pintype "passive"))
      (node (ref "X3") (pin "18") (pinfunction "1_18") (pintype "passive"))
      (node (ref "X3") (pin "19") (pinfunction "1_19") (pintype "passive"))
      (node (ref "X3") (pin "20") (pinfunction "1_20") (pintype "passive"))
      (node (ref "X3") (pin "21") (pinfunction "1_21") (pintype "passive"))
    )
    (net (code "63") (name "PB_ADC") (class "Default")
      (node (ref "MCU") (pin "5") (pinfunction "5(PE3)_5") (pintype "bidirectional"))
      (node (ref "X3") (pin "6") (pinfunction "1_6") (pintype "passive"))
    )
    (net (code "64") (name "PB_DAC") (class "Default")
      (node (ref "MCU") (pin "4") (pinfunction "4(PG5)_4") (pintype "bidirectional"))
      (node (ref "X3") (pin "4") (pinfunction "1_4") (pintype "passive"))
    )
    (net (code "65") (name "PB_EXPANDER") (class "Default")
      (node (ref "MCU") (pin "3") (pinfunction "3(PE5)_3") (pintype "bidirectional"))
      (node (ref "X3") (pin "3") (pinfunction "1_3") (pintype "passive"))
    )
    (net (code "66") (name "PB_LOAD") (class "Default")
      (node (ref "MCU") (pin "11") (pinfunction "11_11") (pintype "bidirectional"))
      (node (ref "Q2") (pin "1") (pinfunction "G_1") (pintype "passive"))
      (node (ref "R10") (pin "2") (pinfunction "2_2") (pintype "passive"))
    )
    (net (code "67") (name "PB_NTC") (class "Default")
      (node (ref "C5") (pin "2") (pinfunction "2_2") (pintype "passive"))
      (node (ref "MCU") (pin "A5") (pinfunction "ADC5_A5") (pintype "bidirectional"))
      (node (ref "R12") (pin "1") (pinfunction "1_1") (pintype "passive"))
      (node (ref "X3") (pin "13") (pinfunction "1_13") (pintype "passive"))
    )
    (net (code "68") (name "PB_OUT_MON") (class "Default")
      (node (ref "IC1") (pin "6") (pinfunction "-IN_6") (pintype "input"))
      (node (ref "IC1") (pin "7") (pinfunction "OUT_7") (pintype "output"))
      (node (ref "MCU") (pin "A4") (pinfunction "ADC4_A4") (pintype "bidirectional"))
    )
    (net (code "69") (name "PB_POWER") (class "Default")
      (node (ref "MCU") (pin "10") (pinfunction "10_10") (pintype "bidirectional"))
      (node (ref "Q3") (pin "1") (pinfunction "G_1") (pintype "passive"))
      (node (ref "R11") (pin "2") (pinfunction "2_2") (pintype "passive"))
    )
    (net (code "70") (name "RPROG") (class "Default")
      (node (ref "MCU") (pin "9") (pinfunction "9(PH6)_9") (pintype "bidirectional"))
      (node (ref "R14") (pin "2") (pinfunction "2_2") (pintype "passive"))
    )
    (net (code "71") (name "SCLK") (class "Default")
      (node (ref "MCU") (pin "ICSP_SCK") (pinfunction "SCK_ICSP_SCK") (pintype "bidirectional"))
      (node (ref "X3") (pin "7") (pinfunction "1_7") (pintype "passive"))
    )
    (net (code "72") (name "SW1") (class "Default")
      (node (ref "C19") (pin "1") (pinfunction "1_1") (pintype "passive"))
      (node (ref "MCU") (pin "7") (pinfunction "7(PH4)_7") (pintype "bidirectional"))
      (node (ref "SW2") (pin "3") (pinfunction "3_3") (pintype "passive"))
      (node (ref "SW2") (pin "4") (pinfunction "4_4") (pintype "passive"))
    )
    (net (code "73") (name "SW2") (class "Default")
      (node (ref "C12") (pin "1") (pinfunction "1_1") (pintype "passive"))
      (node (ref "MCU") (pin "8") (pinfunction "8(PH5)_8") (pintype "bidirectional"))
      (node (ref "SW1") (pin "3") (pinfunction "3_3") (pintype "passive"))
      (node (ref "SW1") (pin "4") (pinfunction "4_4") (pintype "passive"))
    )
    (net (code "74") (name "VCC_AUX") (class "Default")
      (node (ref "MCU") (pin "A2") (pinfunction "ADC2_A2") (pintype "bidirectional"))
      (node (ref "R27") (pin "1") (pinfunction "1_1") (pintype "passive"))
      (node (ref "R32") (pin "2") (pinfunction "2_2") (pintype "passive"))
    )
    (net (code "75") (name "unconnected-(IC2-SYNC-Pad4)") (class "Default")
      (node (ref "IC2") (pin "4") (pinfunction "SYNC_4") (pintype "input"))
    )
    (net (code "76") (name "unconnected-(K1A-S-Pad12A)") (class "Default")
      (node (ref "K1") (pin "12A") (pinfunction "S_12A") (pintype "passive"))
    )
    (net (code "77") (name "unconnected-(K1B-S-Pad12B)") (class "Default")
      (node (ref "K1") (pin "12B") (pinfunction "S_12B") (pintype "passive"))
    )
    (net (code "78") (name "unconnected-(K_DC-PadO)") (class "Default")
      (node (ref "K_DC") (pin "O") (pinfunction "O_O") (pintype "passive"))
    )
    (net (code "79") (name "unconnected-(K_LOAD-PadO)") (class "Default")
      (node (ref "K_LOAD") (pin "O") (pinfunction "O_O") (pintype "passive"))
    )
    (net (code "80") (name "unconnected-(MCU-PadAREF)") (class "Default")
      (node (ref "MCU") (pin "AREF") (pinfunction "AREF_AREF") (pintype "bidirectional"))
    )
    (net (code "81") (name "unconnected-(MCU-PadGND)") (class "Default")
      (node (ref "MCU") (pin "GND") (pinfunction "GND_GND") (pintype "bidirectional"))
    )
    (net (code "82") (name "unconnected-(MCU-PadIOREF)") (class "Default")
      (node (ref "MCU") (pin "IOREF") (pinfunction "IOREF_IOREF") (pintype "bidirectional"))
    )
    (net (code "83") (name "unconnected-(MCU-PadN{slash}C)") (class "Default")
      (node (ref "MCU") (pin "N/C") (pinfunction "N/C_N/C") (pintype "no_connect"))
    )
    (net (code "84") (name "unconnected-(MCU-PadVIN)") (class "Default")
      (node (ref "MCU") (pin "VIN") (pinfunction "VIN_VIN") (pintype "bidirectional"))
    )
    (net (code "85") (name "unconnected-(MCUC-0(PE0)-Pad0)") (class "Default")
      (node (ref "MCU") (pin "0") (pinfunction "0(PE0)_0") (pintype "bidirectional"))
    )
    (net (code "86") (name "unconnected-(MCUD-+5V-PadICSP_+5V)") (class "Default")
      (node (ref "MCU") (pin "ICSP_+5V") (pinfunction "+5V_ICSP_+5V") (pintype "bidirectional"))
    )
    (net (code "87") (name "unconnected-(MCUD-~{RESET}-PadICSP_RESET)") (class "Default")
      (node (ref "MCU") (pin "ICSP_RESET") (pinfunction "~{RESET}_ICSP_RESET") (pintype "bidirectional"))
    )
    (net (code "88") (name "unconnected-(MCUE-~{RESET}-PadRESET)") (class "Default")
      (node (ref "MCU") (pin "RESET") (pinfunction "~{RESET}_RESET") (pintype "bidirectional"))
    )
    (net (code "89") (name "~{PB_INT_ADC}") (class "Default")
      (node (ref "MCU") (pin "2") (pinfunction "2(PE4)_2") (pintype "bidirectional"))
      (node (ref "X3") (pin "8") (pinfunction "1_8") (pintype "passive"))
    )
    (net (code "90") (name "~{PB_RESET_OUT}") (class "Default")
      (node (ref "MCU") (pin "6") (pinfunction "6(PH3)_6") (pintype "bidirectional"))
      (node (ref "X3") (pin "5") (pinfunction "1_5") (pintype "passive"))
    )
  )
)
